# ANALOG_INPUT.net
KiCad netlist of a schematic drawn in Altium Designer
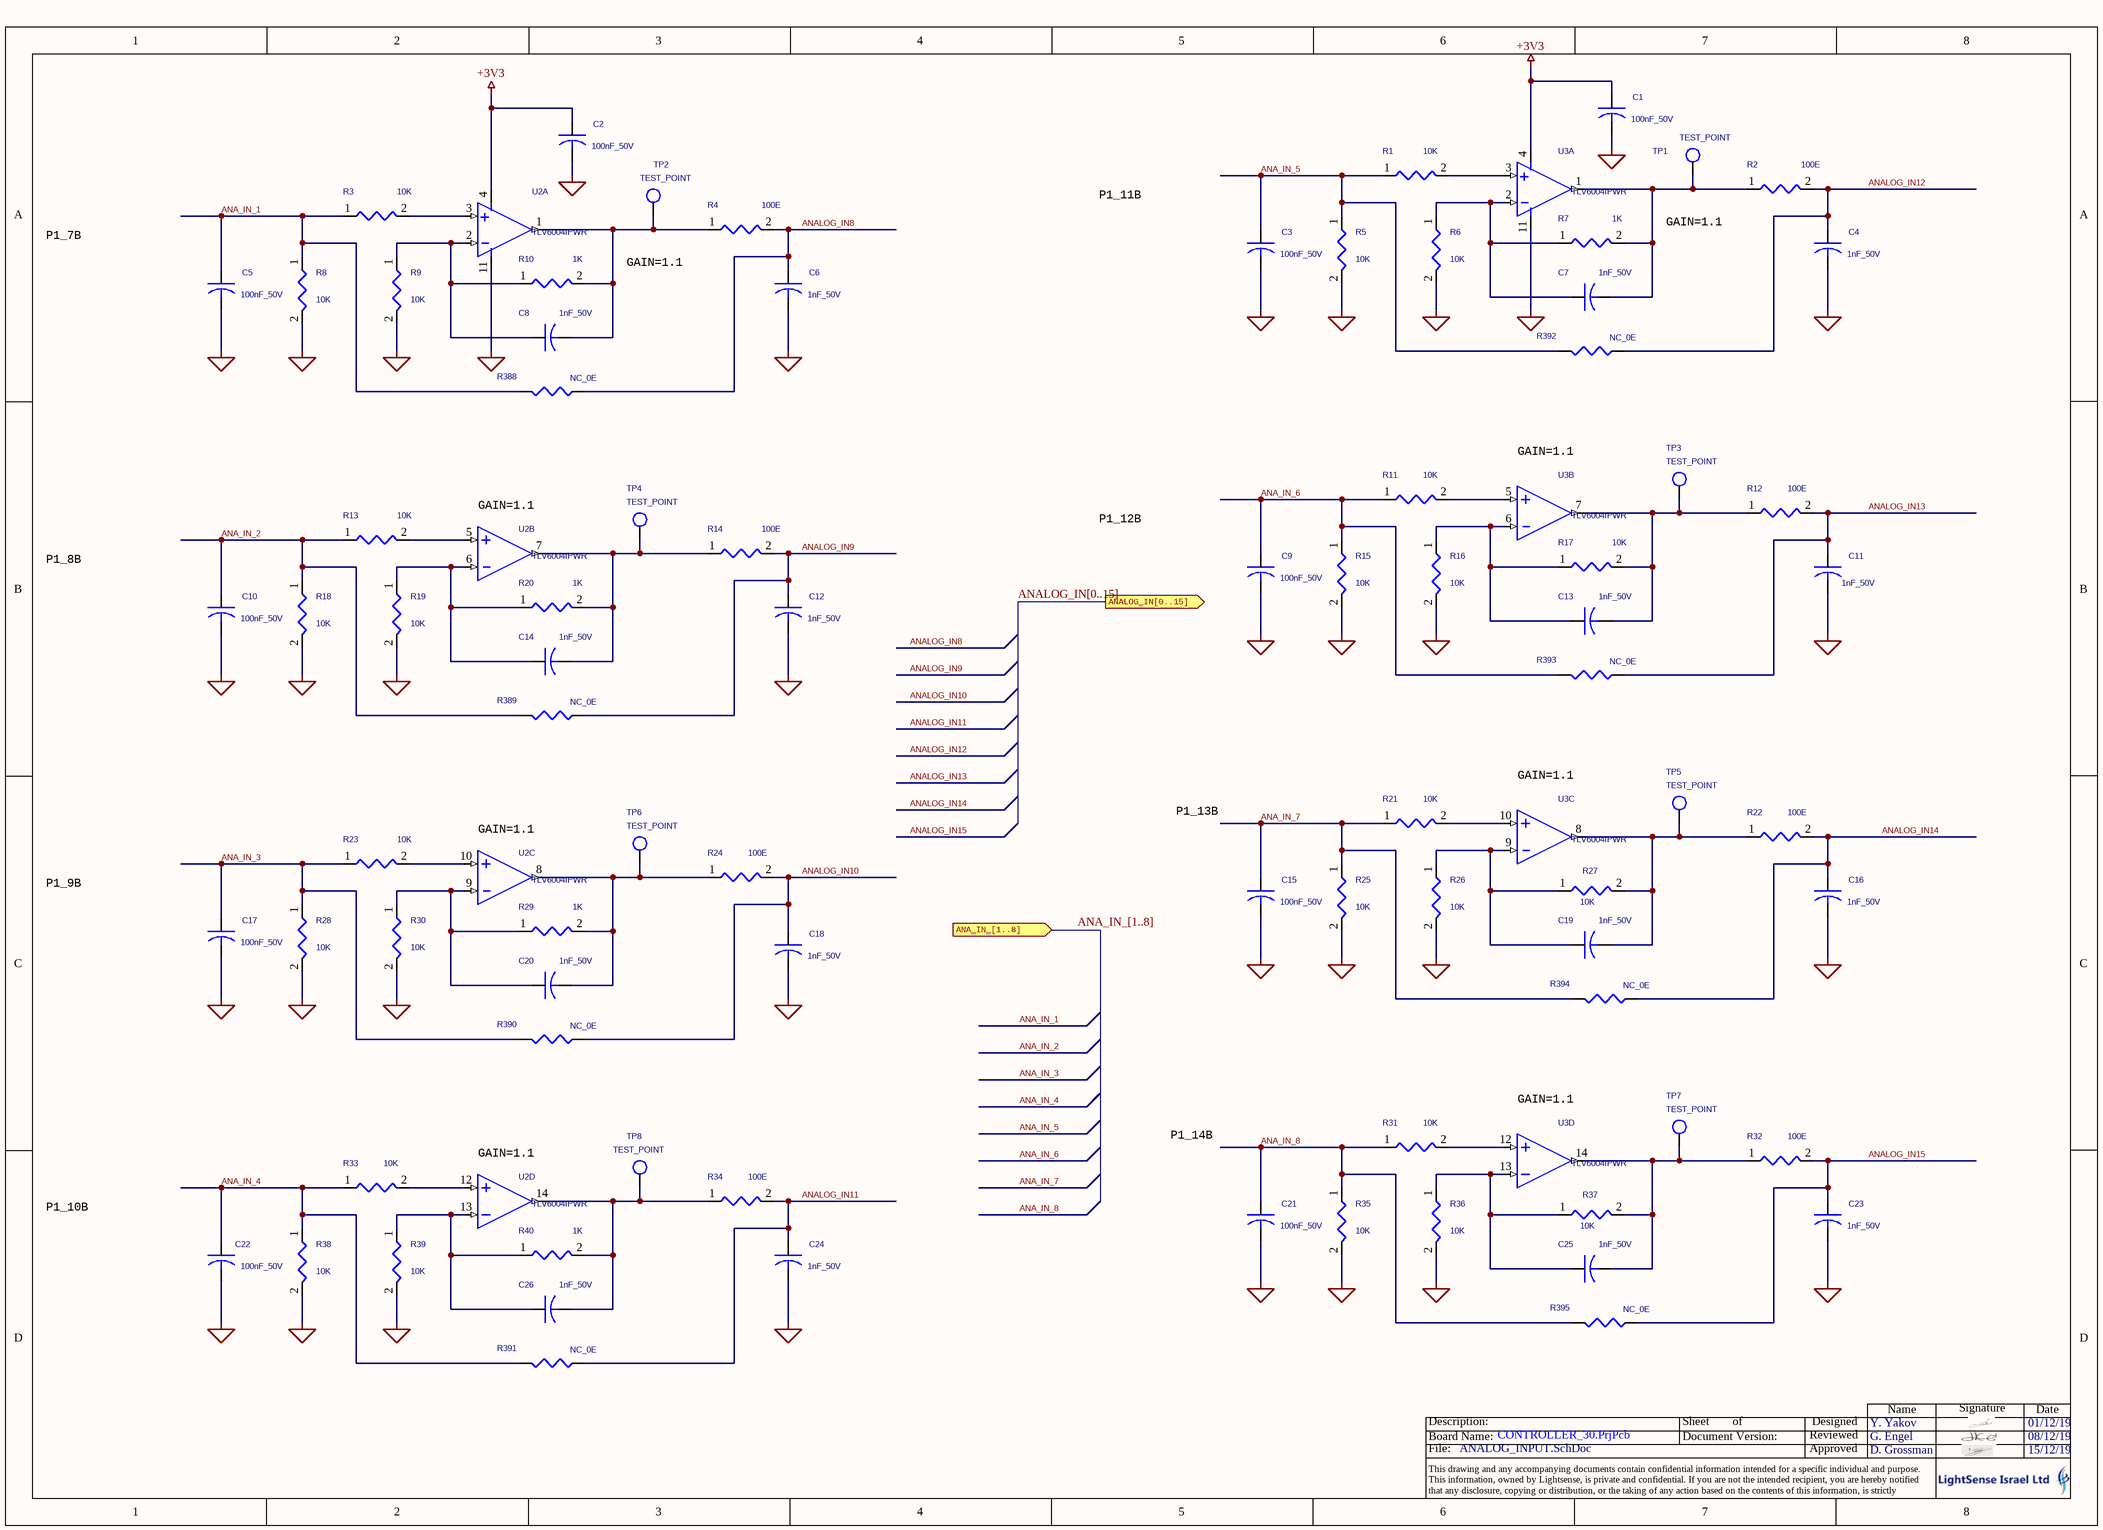
[diagram p0: ANALOG_INPUT.SchDoc]

(export (version "E")
  (design (tool "Eeschema 10.0.6"))
  (components
    (comp (ref "C1")
      (value "100nF_50V")
      (footprint "0603")
      (description "CAP_SMT_0603_50V_X7R_10%")
      (fields (field (name "MFG") "KEMET"))
      (libsource (lib "*") (part "C"))
    )
    (comp (ref "C2")
      (value "100nF_50V")
      (footprint "0603")
      (description "CAP_SMT_0603_50V_X7R_10%")
      (fields (field (name "MFG") "KEMET"))
      (libsource (lib "*") (part "C"))
    )
    (comp (ref "C3")
      (value "100nF_50V")
      (footprint "0603")
      (description "CAP_SMT_0603_50V_X7R_10%")
      (fields (field (name "MFG") "KEMET"))
      (libsource (lib "*") (part "C"))
    )
    (comp (ref "C4")
      (value "1nF_50V")
      (footprint "0603")
      (description "CAP_SMT_0603_50V_X7R_10%")
      (fields (field (name "MFG") "KEMET"))
      (libsource (lib "*") (part "C"))
    )
    (comp (ref "C5")
      (value "100nF_50V")
      (footprint "0603")
      (description "CAP_SMT_0603_50V_X7R_10%")
      (fields (field (name "MFG") "KEMET"))
      (libsource (lib "*") (part "C"))
    )
    (comp (ref "C6")
      (value "1nF_50V")
      (footprint "0603")
      (description "CAP_SMT_0603_50V_X7R_10%")
      (fields (field (name "MFG") "KEMET"))
      (libsource (lib "*") (part "C"))
    )
    (comp (ref "C7")
      (value "1nF_50V")
      (footprint "0603")
      (description "CAP_SMT_0603_50V_X7R_10%")
      (fields (field (name "MFG") "KEMET"))
      (libsource (lib "*") (part "C"))
    )
    (comp (ref "C8")
      (value "1nF_50V")
      (footprint "0603")
      (description "CAP_SMT_0603_50V_X7R_10%")
      (fields (field (name "MFG") "KEMET"))
      (libsource (lib "*") (part "C"))
    )
    (comp (ref "C9")
      (value "100nF_50V")
      (footprint "0603")
      (description "CAP_SMT_0603_50V_X7R_10%")
      (fields (field (name "MFG") "KEMET"))
      (libsource (lib "*") (part "C"))
    )
    (comp (ref "C10")
      (value "100nF_50V")
      (footprint "0603")
      (description "CAP_SMT_0603_50V_X7R_10%")
      (fields (field (name "MFG") "KEMET"))
      (libsource (lib "*") (part "C"))
    )
    (comp (ref "C11")
      (value "1nF_50V")
      (footprint "0603")
      (description "CAP_SMT_0603_50V_X7R_10%")
      (fields (field (name "MFG") "KEMET"))
      (libsource (lib "*") (part "C"))
    )
    (comp (ref "C12")
      (value "1nF_50V")
      (footprint "0603")
      (description "CAP_SMT_0603_50V_X7R_10%")
      (fields (field (name "MFG") "KEMET"))
      (libsource (lib "*") (part "C"))
    )
    (comp (ref "C13")
      (value "1nF_50V")
      (footprint "0603")
      (description "CAP_SMT_0603_50V_X7R_10%")
      (fields (field (name "MFG") "KEMET"))
      (libsource (lib "*") (part "C"))
    )
    (comp (ref "C14")
      (value "1nF_50V")
      (footprint "0603")
      (description "CAP_SMT_0603_50V_X7R_10%")
      (fields (field (name "MFG") "KEMET"))
      (libsource (lib "*") (part "C"))
    )
    (comp (ref "C15")
      (value "100nF_50V")
      (footprint "0603")
      (description "CAP_SMT_0603_50V_X7R_10%")
      (fields (field (name "MFG") "KEMET"))
      (libsource (lib "*") (part "C"))
    )
    (comp (ref "C16")
      (value "1nF_50V")
      (footprint "0603")
      (description "CAP_SMT_0603_50V_X7R_10%")
      (fields (field (name "MFG") "KEMET"))
      (libsource (lib "*") (part "C"))
    )
    (comp (ref "C17")
      (value "100nF_50V")
      (footprint "0603")
      (description "CAP_SMT_0603_50V_X7R_10%")
      (fields (field (name "MFG") "KEMET"))
      (libsource (lib "*") (part "C"))
    )
    (comp (ref "C18")
      (value "1nF_50V")
      (footprint "0603")
      (description "CAP_SMT_0603_50V_X7R_10%")
      (fields (field (name "MFG") "KEMET"))
      (libsource (lib "*") (part "C"))
    )
    (comp (ref "C19")
      (value "1nF_50V")
      (footprint "0603")
      (description "CAP_SMT_0603_50V_X7R_10%")
      (fields (field (name "MFG") "KEMET"))
      (libsource (lib "*") (part "C"))
    )
    (comp (ref "C20")
      (value "1nF_50V")
      (footprint "0603")
      (description "CAP_SMT_0603_50V_X7R_10%")
      (fields (field (name "MFG") "KEMET"))
      (libsource (lib "*") (part "C"))
    )
    (comp (ref "C21")
      (value "100nF_50V")
      (footprint "0603")
      (description "CAP_SMT_0603_50V_X7R_10%")
      (fields (field (name "MFG") "KEMET"))
      (libsource (lib "*") (part "C"))
    )
    (comp (ref "C22")
      (value "100nF_50V")
      (footprint "0603")
      (description "CAP_SMT_0603_50V_X7R_10%")
      (fields (field (name "MFG") "KEMET"))
      (libsource (lib "*") (part "C"))
    )
    (comp (ref "C23")
      (value "1nF_50V")
      (footprint "0603")
      (description "CAP_SMT_0603_50V_X7R_10%")
      (fields (field (name "MFG") "KEMET"))
      (libsource (lib "*") (part "C"))
    )
    (comp (ref "C24")
      (value "1nF_50V")
      (footprint "0603")
      (description "CAP_SMT_0603_50V_X7R_10%")
      (fields (field (name "MFG") "KEMET"))
      (libsource (lib "*") (part "C"))
    )
    (comp (ref "C25")
      (value "1nF_50V")
      (footprint "0603")
      (description "CAP_SMT_0603_50V_X7R_10%")
      (fields (field (name "MFG") "KEMET"))
      (libsource (lib "*") (part "C"))
    )
    (comp (ref "C26")
      (value "1nF_50V")
      (footprint "0603")
      (description "CAP_SMT_0603_50V_X7R_10%")
      (fields (field (name "MFG") "KEMET"))
      (libsource (lib "*") (part "C"))
    )
    (comp (ref "R1")
      (value "10K")
      (footprint "0603")
      (fields (field (name "MFG") "YAGEO"))
      (libsource (lib "*") (part "R_Dup2"))
    )
    (comp (ref "R2")
      (value "100E")
      (footprint "0603")
      (fields (field (name "MFG") "YAGEO"))
      (libsource (lib "*") (part "R_Dup2"))
    )
    (comp (ref "R3")
      (value "10K")
      (footprint "0603")
      (fields (field (name "MFG") "YAGEO"))
      (libsource (lib "*") (part "R_Dup2"))
    )
    (comp (ref "R4")
      (value "100E")
      (footprint "0603")
      (fields (field (name "MFG") "YAGEO"))
      (libsource (lib "*") (part "R_Dup2"))
    )
    (comp (ref "R5")
      (value "10K")
      (footprint "0603")
      (fields (field (name "MFG") "YAGEO"))
      (libsource (lib "*") (part "R_Dup2"))
    )
    (comp (ref "R6")
      (value "10K")
      (footprint "0603")
      (fields (field (name "MFG") "YAGEO"))
      (libsource (lib "*") (part "R_Dup2"))
    )
    (comp (ref "R7")
      (value "1K")
      (footprint "0603")
      (fields (field (name "MFG") "YAGEO"))
      (libsource (lib "*") (part "R_Dup2"))
    )
    (comp (ref "R8")
      (value "10K")
      (footprint "0603")
      (fields (field (name "MFG") "YAGEO"))
      (libsource (lib "*") (part "R_Dup2"))
    )
    (comp (ref "R9")
      (value "10K")
      (footprint "0603")
      (fields (field (name "MFG") "YAGEO"))
      (libsource (lib "*") (part "R_Dup2"))
    )
    (comp (ref "R10")
      (value "1K")
      (footprint "0603")
      (fields (field (name "MFG") "YAGEO"))
      (libsource (lib "*") (part "R_Dup2"))
    )
    (comp (ref "R11")
      (value "10K")
      (footprint "0603")
      (fields (field (name "MFG") "YAGEO"))
      (libsource (lib "*") (part "R_Dup2"))
    )
    (comp (ref "R12")
      (value "100E")
      (footprint "0603")
      (fields (field (name "MFG") "YAGEO"))
      (libsource (lib "*") (part "R_Dup2"))
    )
    (comp (ref "R13")
      (value "10K")
      (footprint "0603")
      (fields (field (name "MFG") "YAGEO"))
      (libsource (lib "*") (part "R_Dup2"))
    )
    (comp (ref "R14")
      (value "100E")
      (footprint "0603")
      (fields (field (name "MFG") "YAGEO"))
      (libsource (lib "*") (part "R_Dup2"))
    )
    (comp (ref "R15")
      (value "10K")
      (footprint "0603")
      (fields (field (name "MFG") "YAGEO"))
      (libsource (lib "*") (part "R_Dup2"))
    )
    (comp (ref "R16")
      (value "10K")
      (footprint "0603")
      (fields (field (name "MFG") "YAGEO"))
      (libsource (lib "*") (part "R_Dup2"))
    )
    (comp (ref "R17")
      (value "10K")
      (footprint "0603")
      (fields (field (name "MFG") "YAGEO"))
      (libsource (lib "*") (part "R_Dup2"))
    )
    (comp (ref "R18")
      (value "10K")
      (footprint "0603")
      (fields (field (name "MFG") "YAGEO"))
      (libsource (lib "*") (part "R_Dup2"))
    )
    (comp (ref "R19")
      (value "10K")
      (footprint "0603")
      (fields (field (name "MFG") "YAGEO"))
      (libsource (lib "*") (part "R_Dup2"))
    )
    (comp (ref "R20")
      (value "1K")
      (footprint "0603")
      (fields (field (name "MFG") "YAGEO"))
      (libsource (lib "*") (part "R_Dup2"))
    )
    (comp (ref "R21")
      (value "10K")
      (footprint "0603")
      (fields (field (name "MFG") "YAGEO"))
      (libsource (lib "*") (part "R_Dup2"))
    )
    (comp (ref "R22")
      (value "100E")
      (footprint "0603")
      (fields (field (name "MFG") "YAGEO"))
      (libsource (lib "*") (part "R_Dup2"))
    )
    (comp (ref "R23")
      (value "10K")
      (footprint "0603")
      (fields (field (name "MFG") "YAGEO"))
      (libsource (lib "*") (part "R_Dup2"))
    )
    (comp (ref "R24")
      (value "100E")
      (footprint "0603")
      (fields (field (name "MFG") "YAGEO"))
      (libsource (lib "*") (part "R_Dup2"))
    )
    (comp (ref "R25")
      (value "10K")
      (footprint "0603")
      (fields (field (name "MFG") "YAGEO"))
      (libsource (lib "*") (part "R_Dup2"))
    )
    (comp (ref "R26")
      (value "10K")
      (footprint "0603")
      (fields (field (name "MFG") "YAGEO"))
      (libsource (lib "*") (part "R_Dup2"))
    )
    (comp (ref "R27")
      (value "10K")
      (footprint "0603")
      (fields (field (name "MFG") "YAGEO"))
      (libsource (lib "*") (part "R_Dup2"))
    )
    (comp (ref "R28")
      (value "10K")
      (footprint "0603")
      (fields (field (name "MFG") "YAGEO"))
      (libsource (lib "*") (part "R_Dup2"))
    )
    (comp (ref "R29")
      (value "1K")
      (footprint "0603")
      (fields (field (name "MFG") "YAGEO"))
      (libsource (lib "*") (part "R_Dup2"))
    )
    (comp (ref "R30")
      (value "10K")
      (footprint "0603")
      (fields (field (name "MFG") "YAGEO"))
      (libsource (lib "*") (part "R_Dup2"))
    )
    (comp (ref "R31")
      (value "10K")
      (footprint "0603")
      (fields (field (name "MFG") "YAGEO"))
      (libsource (lib "*") (part "R_Dup2"))
    )
    (comp (ref "R32")
      (value "100E")
      (footprint "0603")
      (fields (field (name "MFG") "YAGEO"))
      (libsource (lib "*") (part "R_Dup2"))
    )
    (comp (ref "R33")
      (value "10K")
      (footprint "0603")
      (fields (field (name "MFG") "YAGEO"))
      (libsource (lib "*") (part "R_Dup2"))
    )
    (comp (ref "R34")
      (value "100E")
      (footprint "0603")
      (fields (field (name "MFG") "YAGEO"))
      (libsource (lib "*") (part "R_Dup2"))
    )
    (comp (ref "R35")
      (value "10K")
      (footprint "0603")
      (fields (field (name "MFG") "YAGEO"))
      (libsource (lib "*") (part "R_Dup2"))
    )
    (comp (ref "R36")
      (value "10K")
      (footprint "0603")
      (fields (field (name "MFG") "YAGEO"))
      (libsource (lib "*") (part "R_Dup2"))
    )
    (comp (ref "R37")
      (value "10K")
      (footprint "0603")
      (fields (field (name "MFG") "YAGEO"))
      (libsource (lib "*") (part "R_Dup2"))
    )
    (comp (ref "R38")
      (value "10K")
      (footprint "0603")
      (fields (field (name "MFG") "YAGEO"))
      (libsource (lib "*") (part "R_Dup2"))
    )
    (comp (ref "R39")
      (value "10K")
      (footprint "0603")
      (fields (field (name "MFG") "YAGEO"))
      (libsource (lib "*") (part "R_Dup2"))
    )
    (comp (ref "R40")
      (value "1K")
      (footprint "0603")
      (fields (field (name "MFG") "YAGEO"))
      (libsource (lib "*") (part "R_Dup2"))
    )
    (comp (ref "R388")
      (value "NC_0E")
      (footprint "0603")
      (fields (field (name "MFG") "YAGEO"))
      (libsource (lib "*") (part "R_Dup1"))
    )
    (comp (ref "R389")
      (value "NC_0E")
      (footprint "0603")
      (fields (field (name "MFG") "YAGEO"))
      (libsource (lib "*") (part "R_Dup1"))
    )
    (comp (ref "R390")
      (value "NC_0E")
      (footprint "0603")
      (fields (field (name "MFG") "YAGEO"))
      (libsource (lib "*") (part "R_Dup1"))
    )
    (comp (ref "R391")
      (value "NC_0E")
      (footprint "0603")
      (fields (field (name "MFG") "YAGEO"))
      (libsource (lib "*") (part "R_Dup1"))
    )
    (comp (ref "R392")
      (value "NC_0E")
      (footprint "0603")
      (fields (field (name "MFG") "YAGEO"))
      (libsource (lib "*") (part "R_Dup1"))
    )
    (comp (ref "R393")
      (value "NC_0E")
      (footprint "0603")
      (fields (field (name "MFG") "YAGEO"))
      (libsource (lib "*") (part "R_Dup1"))
    )
    (comp (ref "R394")
      (value "NC_0E")
      (footprint "0603")
      (fields (field (name "MFG") "YAGEO"))
      (libsource (lib "*") (part "R_Dup1"))
    )
    (comp (ref "R395")
      (value "NC_0E")
      (footprint "0603")
      (fields (field (name "MFG") "YAGEO"))
      (libsource (lib "*") (part "R_Dup1"))
    )
    (comp (ref "TP1") (value "TEST_POINT") (footprint "TH_1mm") (libsource (lib "*") (part "T POINT R_Dup1")))
    (comp (ref "TP2") (value "TEST_POINT") (footprint "TH_1mm") (libsource (lib "*") (part "T POINT R_Dup1")))
    (comp (ref "TP3") (value "TEST_POINT") (footprint "TH_1mm") (libsource (lib "*") (part "T POINT R_Dup1")))
    (comp (ref "TP4") (value "TEST_POINT") (footprint "TH_1mm") (libsource (lib "*") (part "T POINT R_Dup1")))
    (comp (ref "TP5") (value "TEST_POINT") (footprint "TH_1mm") (libsource (lib "*") (part "T POINT R_Dup1")))
    (comp (ref "TP6") (value "TEST_POINT") (footprint "TH_1mm") (libsource (lib "*") (part "T POINT R_Dup1")))
    (comp (ref "TP7") (value "TEST_POINT") (footprint "TH_1mm") (libsource (lib "*") (part "T POINT R_Dup1")))
    (comp (ref "TP8") (value "TEST_POINT") (footprint "TH_1mm") (libsource (lib "*") (part "T POINT R_Dup1")))
    (comp (ref "U2")
      (value "TLV6004IPWR")
      (footprint "TSSOP_14")
      (description "OP_AMP")
      (fields (field (name "MFG") "TI"))
      (libsource (lib "*") (part "TL6004IP"))
    )
    (comp (ref "U3")
      (value "TLV6004IPWR")
      (footprint "TSSOP_14")
      (description "OP_AMP")
      (fields (field (name "MFG") "TI"))
      (libsource (lib "*") (part "TL6004IP"))
    )
  )
  (nets
    (net (code "9") (name "+3V3") (class "Default")
      (node (ref "C1") (pin "1") (pinfunction "1_1") (pintype "passive"))
      (node (ref "C2") (pin "1") (pinfunction "1_1") (pintype "passive"))
      (node (ref "U2") (pin "4") (pinfunction "VCC_4") (pintype "passive"))
      (node (ref "U3") (pin "4") (pinfunction "VCC_4") (pintype "passive"))
    )
    (net (code "10") (name "/ANALOG_IN8") (class "Default")
      (node (ref "C6") (pin "1") (pinfunction "1_1") (pintype "passive"))
      (node (ref "R388") (pin "1") (pinfunction "1_1") (pintype "passive"))
      (node (ref "R4") (pin "2") (pinfunction "2_2") (pintype "passive"))
    )
    (net (code "11") (name "/ANALOG_IN9") (class "Default")
      (node (ref "C12") (pin "1") (pinfunction "1_1") (pintype "passive"))
      (node (ref "R14") (pin "2") (pinfunction "2_2") (pintype "passive"))
      (node (ref "R389") (pin "1") (pinfunction "1_1") (pintype "passive"))
    )
    (net (code "12") (name "/ANALOG_IN10") (class "Default")
      (node (ref "C18") (pin "1") (pinfunction "1_1") (pintype "passive"))
      (node (ref "R24") (pin "2") (pinfunction "2_2") (pintype "passive"))
      (node (ref "R390") (pin "1") (pinfunction "1_1") (pintype "passive"))
    )
    (net (code "13") (name "/ANALOG_IN11") (class "Default")
      (node (ref "C24") (pin "1") (pinfunction "1_1") (pintype "passive"))
      (node (ref "R34") (pin "2") (pinfunction "2_2") (pintype "passive"))
      (node (ref "R391") (pin "1") (pinfunction "1_1") (pintype "passive"))
    )
    (net (code "14") (name "/ANALOG_IN12") (class "Default")
      (node (ref "C4") (pin "1") (pinfunction "1_1") (pintype "passive"))
      (node (ref "R2") (pin "2") (pinfunction "2_2") (pintype "passive"))
      (node (ref "R392") (pin "1") (pinfunction "1_1") (pintype "passive"))
    )
    (net (code "15") (name "/ANALOG_IN13") (class "Default")
      (node (ref "C11") (pin "1") (pinfunction "1_1") (pintype "passive"))
      (node (ref "R12") (pin "2") (pinfunction "2_2") (pintype "passive"))
      (node (ref "R393") (pin "1") (pinfunction "1_1") (pintype "passive"))
    )
    (net (code "16") (name "/ANALOG_IN14") (class "Default")
      (node (ref "C16") (pin "1") (pinfunction "1_1") (pintype "passive"))
      (node (ref "R22") (pin "2") (pinfunction "2_2") (pintype "passive"))
      (node (ref "R394") (pin "1") (pinfunction "1_1") (pintype "passive"))
    )
    (net (code "17") (name "/ANALOG_IN15") (class "Default")
      (node (ref "C23") (pin "1") (pinfunction "1_1") (pintype "passive"))
      (node (ref "R32") (pin "2") (pinfunction "2_2") (pintype "passive"))
      (node (ref "R395") (pin "1") (pinfunction "1_1") (pintype "passive"))
    )
    (net (code "19") (name "/ANA_IN_1") (class "Default")
      (node (ref "C5") (pin "1") (pinfunction "1_1") (pintype "passive"))
      (node (ref "R3") (pin "1") (pinfunction "1_1") (pintype "passive"))
      (node (ref "R388") (pin "2") (pinfunction "2_2") (pintype "passive"))
      (node (ref "R8") (pin "1") (pinfunction "1_1") (pintype "passive"))
    )
    (net (code "20") (name "/ANA_IN_2") (class "Default")
      (node (ref "C10") (pin "1") (pinfunction "1_1") (pintype "passive"))
      (node (ref "R13") (pin "1") (pinfunction "1_1") (pintype "passive"))
      (node (ref "R18") (pin "1") (pinfunction "1_1") (pintype "passive"))
      (node (ref "R389") (pin "2") (pinfunction "2_2") (pintype "passive"))
    )
    (net (code "21") (name "/ANA_IN_3") (class "Default")
      (node (ref "C17") (pin "1") (pinfunction "1_1") (pintype "passive"))
      (node (ref "R23") (pin "1") (pinfunction "1_1") (pintype "passive"))
      (node (ref "R28") (pin "1") (pinfunction "1_1") (pintype "passive"))
      (node (ref "R390") (pin "2") (pinfunction "2_2") (pintype "passive"))
    )
    (net (code "22") (name "/ANA_IN_4") (class "Default")
      (node (ref "C22") (pin "1") (pinfunction "1_1") (pintype "passive"))
      (node (ref "R33") (pin "1") (pinfunction "1_1") (pintype "passive"))
      (node (ref "R38") (pin "1") (pinfunction "1_1") (pintype "passive"))
      (node (ref "R391") (pin "2") (pinfunction "2_2") (pintype "passive"))
    )
    (net (code "23") (name "/ANA_IN_5") (class "Default")
      (node (ref "C3") (pin "1") (pinfunction "1_1") (pintype "passive"))
      (node (ref "R1") (pin "1") (pinfunction "1_1") (pintype "passive"))
      (node (ref "R392") (pin "2") (pinfunction "2_2") (pintype "passive"))
      (node (ref "R5") (pin "1") (pinfunction "1_1") (pintype "passive"))
    )
    (net (code "24") (name "/ANA_IN_6") (class "Default")
      (node (ref "C9") (pin "1") (pinfunction "1_1") (pintype "passive"))
      (node (ref "R11") (pin "1") (pinfunction "1_1") (pintype "passive"))
      (node (ref "R15") (pin "1") (pinfunction "1_1") (pintype "passive"))
      (node (ref "R393") (pin "2") (pinfunction "2_2") (pintype "passive"))
    )
    (net (code "25") (name "/ANA_IN_7") (class "Default")
      (node (ref "C15") (pin "1") (pinfunction "1_1") (pintype "passive"))
      (node (ref "R21") (pin "1") (pinfunction "1_1") (pintype "passive"))
      (node (ref "R25") (pin "1") (pinfunction "1_1") (pintype "passive"))
      (node (ref "R394") (pin "2") (pinfunction "2_2") (pintype "passive"))
    )
    (net (code "26") (name "/ANA_IN_8") (class "Default")
      (node (ref "C21") (pin "1") (pinfunction "1_1") (pintype "passive"))
      (node (ref "R31") (pin "1") (pinfunction "1_1") (pintype "passive"))
      (node (ref "R35") (pin "1") (pinfunction "1_1") (pintype "passive"))
      (node (ref "R395") (pin "2") (pinfunction "2_2") (pintype "passive"))
    )
    (net (code "28") (name "AGND") (class "Default")
      (node (ref "C1") (pin "2") (pinfunction "2_2") (pintype "passive"))
      (node (ref "C10") (pin "2") (pinfunction "2_2") (pintype "passive"))
      (node (ref "C11") (pin "2") (pinfunction "2_2") (pintype "passive"))
      (node (ref "C12") (pin "2") (pinfunction "2_2") (pintype "passive"))
      (node (ref "C15") (pin "2") (pinfunction "2_2") (pintype "passive"))
      (node (ref "C16") (pin "2") (pinfunction "2_2") (pintype "passive"))
      (node (ref "C17") (pin "2") (pinfunction "2_2") (pintype "passive"))
      (node (ref "C18") (pin "2") (pinfunction "2_2") (pintype "passive"))
      (node (ref "C2") (pin "2") (pinfunction "2_2") (pintype "passive"))
      (node (ref "C21") (pin "2") (pinfunction "2_2") (pintype "passive"))
      (node (ref "C22") (pin "2") (pinfunction "2_2") (pintype "passive"))
      (node (ref "C23") (pin "2") (pinfunction "2_2") (pintype "passive"))
      (node (ref "C24") (pin "2") (pinfunction "2_2") (pintype "passive"))
      (node (ref "C3") (pin "2") (pinfunction "2_2") (pintype "passive"))
      (node (ref "C4") (pin "2") (pinfunction "2_2") (pintype "passive"))
      (node (ref "C5") (pin "2") (pinfunction "2_2") (pintype "passive"))
      (node (ref "C6") (pin "2") (pinfunction "2_2") (pintype "passive"))
      (node (ref "C9") (pin "2") (pinfunction "2_2") (pintype "passive"))
      (node (ref "R15") (pin "2") (pinfunction "2_2") (pintype "passive"))
      (node (ref "R16") (pin "2") (pinfunction "2_2") (pintype "passive"))
      (node (ref "R18") (pin "2") (pinfunction "2_2") (pintype "passive"))
      (node (ref "R19") (pin "2") (pinfunction "2_2") (pintype "passive"))
      (node (ref "R25") (pin "2") (pinfunction "2_2") (pintype "passive"))
      (node (ref "R26") (pin "2") (pinfunction "2_2") (pintype "passive"))
      (node (ref "R28") (pin "2") (pinfunction "2_2") (pintype "passive"))
      (node (ref "R30") (pin "2") (pinfunction "2_2") (pintype "passive"))
      (node (ref "R35") (pin "2") (pinfunction "2_2") (pintype "passive"))
      (node (ref "R36") (pin "2") (pinfunction "2_2") (pintype "passive"))
      (node (ref "R38") (pin "2") (pinfunction "2_2") (pintype "passive"))
      (node (ref "R39") (pin "2") (pinfunction "2_2") (pintype "passive"))
      (node (ref "R5") (pin "2") (pinfunction "2_2") (pintype "passive"))
      (node (ref "R6") (pin "2") (pinfunction "2_2") (pintype "passive"))
      (node (ref "R8") (pin "2") (pinfunction "2_2") (pintype "passive"))
      (node (ref "R9") (pin "2") (pinfunction "2_2") (pintype "passive"))
      (node (ref "U2") (pin "11") (pinfunction "VEE_11") (pintype "passive"))
      (node (ref "U3") (pin "11") (pinfunction "VEE_11") (pintype "passive"))
    )
    (net (code "29") (name "Net-(TP1-TP)") (class "Default")
      (node (ref "C7") (pin "2") (pinfunction "2_2") (pintype "passive"))
      (node (ref "R2") (pin "1") (pinfunction "1_1") (pintype "passive"))
      (node (ref "R7") (pin "2") (pinfunction "2_2") (pintype "passive"))
      (node (ref "TP1") (pin "1") (pinfunction "TP_1") (pintype "passive"))
      (node (ref "U3") (pin "1") (pinfunction "OA_1") (pintype "output"))
    )
    (net (code "30") (name "Net-(TP2-TP)") (class "Default")
      (node (ref "C8") (pin "2") (pinfunction "2_2") (pintype "passive"))
      (node (ref "R10") (pin "2") (pinfunction "2_2") (pintype "passive"))
      (node (ref "R4") (pin "1") (pinfunction "1_1") (pintype "passive"))
      (node (ref "TP2") (pin "1") (pinfunction "TP_1") (pintype "passive"))
      (node (ref "U2") (pin "1") (pinfunction "OA_1") (pintype "output"))
    )
    (net (code "31") (name "Net-(TP3-TP)") (class "Default")
      (node (ref "C13") (pin "2") (pinfunction "2_2") (pintype "passive"))
      (node (ref "R12") (pin "1") (pinfunction "1_1") (pintype "passive"))
      (node (ref "R17") (pin "2") (pinfunction "2_2") (pintype "passive"))
      (node (ref "TP3") (pin "1") (pinfunction "TP_1") (pintype "passive"))
      (node (ref "U3") (pin "7") (pinfunction "OB_7") (pintype "output"))
    )
    (net (code "32") (name "Net-(TP4-TP)") (class "Default")
      (node (ref "C14") (pin "2") (pinfunction "2_2") (pintype "passive"))
      (node (ref "R14") (pin "1") (pinfunction "1_1") (pintype "passive"))
      (node (ref "R20") (pin "2") (pinfunction "2_2") (pintype "passive"))
      (node (ref "TP4") (pin "1") (pinfunction "TP_1") (pintype "passive"))
      (node (ref "U2") (pin "7") (pinfunction "OB_7") (pintype "output"))
    )
    (net (code "33") (name "Net-(TP5-TP)") (class "Default")
      (node (ref "C19") (pin "2") (pinfunction "2_2") (pintype "passive"))
      (node (ref "R22") (pin "1") (pinfunction "1_1") (pintype "passive"))
      (node (ref "R27") (pin "2") (pinfunction "2_2") (pintype "passive"))
      (node (ref "TP5") (pin "1") (pinfunction "TP_1") (pintype "passive"))
      (node (ref "U3") (pin "8") (pinfunction "OC_8") (pintype "output"))
    )
    (net (code "34") (name "Net-(TP6-TP)") (class "Default")
      (node (ref "C20") (pin "2") (pinfunction "2_2") (pintype "passive"))
      (node (ref "R24") (pin "1") (pinfunction "1_1") (pintype "passive"))
      (node (ref "R29") (pin "2") (pinfunction "2_2") (pintype "passive"))
      (node (ref "TP6") (pin "1") (pinfunction "TP_1") (pintype "passive"))
      (node (ref "U2") (pin "8") (pinfunction "OC_8") (pintype "output"))
    )
    (net (code "35") (name "Net-(TP7-TP)") (class "Default")
      (node (ref "C25") (pin "2") (pinfunction "2_2") (pintype "passive"))
      (node (ref "R32") (pin "1") (pinfunction "1_1") (pintype "passive"))
      (node (ref "R37") (pin "2") (pinfunction "2_2") (pintype "passive"))
      (node (ref "TP7") (pin "1") (pinfunction "TP_1") (pintype "passive"))
      (node (ref "U3") (pin "14") (pinfunction "OD_14") (pintype "output"))
    )
    (net (code "36") (name "Net-(TP8-TP)") (class "Default")
      (node (ref "C26") (pin "2") (pinfunction "2_2") (pintype "passive"))
      (node (ref "R34") (pin "1") (pinfunction "1_1") (pintype "passive"))
      (node (ref "R40") (pin "2") (pinfunction "2_2") (pintype "passive"))
      (node (ref "TP8") (pin "1") (pinfunction "TP_1") (pintype "passive"))
      (node (ref "U2") (pin "14") (pinfunction "OD_14") (pintype "output"))
    )
    (net (code "37") (name "Net-(U2A-IAN)") (class "Default")
      (node (ref "C8") (pin "1") (pinfunction "1_1") (pintype "passive"))
      (node (ref "R10") (pin "1") (pinfunction "1_1") (pintype "passive"))
      (node (ref "R9") (pin "1") (pinfunction "1_1") (pintype "passive"))
      (node (ref "U2") (pin "2") (pinfunction "IAN_2") (pintype "input"))
    )
    (net (code "38") (name "Net-(U2A-IAP)") (class "Default")
      (node (ref "R3") (pin "2") (pinfunction "2_2") (pintype "passive"))
      (node (ref "U2") (pin "3") (pinfunction "IAP_3") (pintype "input"))
    )
    (net (code "39") (name "Net-(U2B-IBN)") (class "Default")
      (node (ref "C14") (pin "1") (pinfunction "1_1") (pintype "passive"))
      (node (ref "R19") (pin "1") (pinfunction "1_1") (pintype "passive"))
      (node (ref "R20") (pin "1") (pinfunction "1_1") (pintype "passive"))
      (node (ref "U2") (pin "6") (pinfunction "IBN_6") (pintype "input"))
    )
    (net (code "40") (name "Net-(U2B-IBP)") (class "Default")
      (node (ref "R13") (pin "2") (pinfunction "2_2") (pintype "passive"))
      (node (ref "U2") (pin "5") (pinfunction "IBP_5") (pintype "input"))
    )
    (net (code "41") (name "Net-(U2C-ICN)") (class "Default")
      (node (ref "C20") (pin "1") (pinfunction "1_1") (pintype "passive"))
      (node (ref "R29") (pin "1") (pinfunction "1_1") (pintype "passive"))
      (node (ref "R30") (pin "1") (pinfunction "1_1") (pintype "passive"))
      (node (ref "U2") (pin "9") (pinfunction "ICN_9") (pintype "input"))
    )
    (net (code "42") (name "Net-(U2C-ICP)") (class "Default")
      (node (ref "R23") (pin "2") (pinfunction "2_2") (pintype "passive"))
      (node (ref "U2") (pin "10") (pinfunction "ICP_10") (pintype "input"))
    )
    (net (code "43") (name "Net-(U2D-IDN)") (class "Default")
      (node (ref "C26") (pin "1") (pinfunction "1_1") (pintype "passive"))
      (node (ref "R39") (pin "1") (pinfunction "1_1") (pintype "passive"))
      (node (ref "R40") (pin "1") (pinfunction "1_1") (pintype "passive"))
      (node (ref "U2") (pin "13") (pinfunction "IDN_13") (pintype "input"))
    )
    (net (code "44") (name "Net-(U2D-IDP)") (class "Default")
      (node (ref "R33") (pin "2") (pinfunction "2_2") (pintype "passive"))
      (node (ref "U2") (pin "12") (pinfunction "IDP_12") (pintype "input"))
    )
    (net (code "45") (name "Net-(U3A-IAN)") (class "Default")
      (node (ref "C7") (pin "1") (pinfunction "1_1") (pintype "passive"))
      (node (ref "R6") (pin "1") (pinfunction "1_1") (pintype "passive"))
      (node (ref "R7") (pin "1") (pinfunction "1_1") (pintype "passive"))
      (node (ref "U3") (pin "2") (pinfunction "IAN_2") (pintype "input"))
    )
    (net (code "46") (name "Net-(U3A-IAP)") (class "Default")
      (node (ref "R1") (pin "2") (pinfunction "2_2") (pintype "passive"))
      (node (ref "U3") (pin "3") (pinfunction "IAP_3") (pintype "input"))
    )
    (net (code "47") (name "Net-(U3B-IBN)") (class "Default")
      (node (ref "C13") (pin "1") (pinfunction "1_1") (pintype "passive"))
      (node (ref "R16") (pin "1") (pinfunction "1_1") (pintype "passive"))
      (node (ref "R17") (pin "1") (pinfunction "1_1") (pintype "passive"))
      (node (ref "U3") (pin "6") (pinfunction "IBN_6") (pintype "input"))
    )
    (net (code "48") (name "Net-(U3B-IBP)") (class "Default")
      (node (ref "R11") (pin "2") (pinfunction "2_2") (pintype "passive"))
      (node (ref "U3") (pin "5") (pinfunction "IBP_5") (pintype "input"))
    )
    (net (code "49") (name "Net-(U3C-ICN)") (class "Default")
      (node (ref "C19") (pin "1") (pinfunction "1_1") (pintype "passive"))
      (node (ref "R26") (pin "1") (pinfunction "1_1") (pintype "passive"))
      (node (ref "R27") (pin "1") (pinfunction "1_1") (pintype "passive"))
      (node (ref "U3") (pin "9") (pinfunction "ICN_9") (pintype "input"))
    )
    (net (code "50") (name "Net-(U3C-ICP)") (class "Default")
      (node (ref "R21") (pin "2") (pinfunction "2_2") (pintype "passive"))
      (node (ref "U3") (pin "10") (pinfunction "ICP_10") (pintype "input"))
    )
    (net (code "51") (name "Net-(U3D-IDN)") (class "Default")
      (node (ref "C25") (pin "1") (pinfunction "1_1") (pintype "passive"))
      (node (ref "R36") (pin "1") (pinfunction "1_1") (pintype "passive"))
      (node (ref "R37") (pin "1") (pinfunction "1_1") (pintype "passive"))
      (node (ref "U3") (pin "13") (pinfunction "IDN_13") (pintype "input"))
    )
    (net (code "52") (name "Net-(U3D-IDP)") (class "Default")
      (node (ref "R31") (pin "2") (pinfunction "2_2") (pintype "passive"))
      (node (ref "U3") (pin "12") (pinfunction "IDP_12") (pintype "input"))
    )
  )
)
